# UAV_ARM.net
KiCad netlist of a schematic drawn in EAGLE
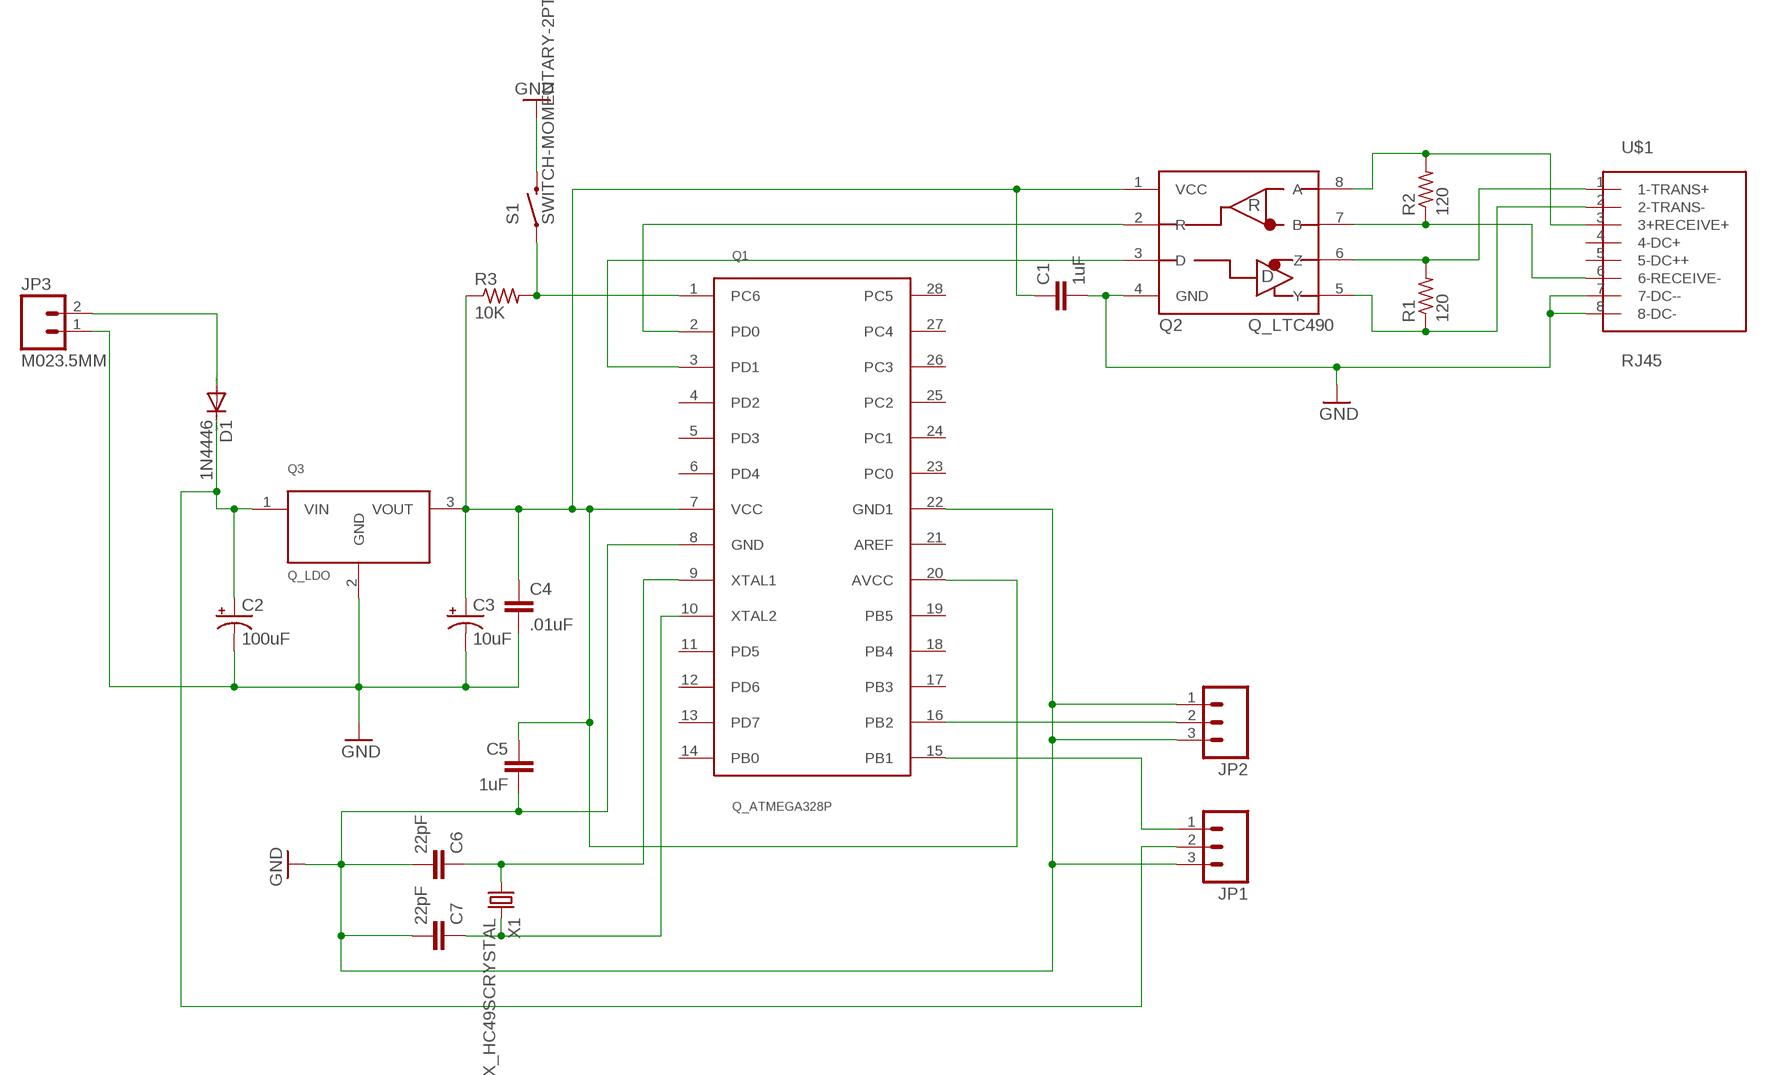
[diagram p0: schematic, sheet 1]

(export (version "E")
  (design (tool "Eeschema 10.0.6"))
  (components
    (comp (ref "C1")
      (value "1uF")
      (footprint "eagle-import:CAP-PTH-SMALL-KIT")
      (libsource (lib "eagle-import") (part "CAPKIT"))
    )
    (comp (ref "C2")
      (value "100uF")
      (footprint "eagle-import:CPOL-RADIAL-100UF-25V")
      (libsource (lib "eagle-import") (part "CAP_POLPTH1"))
    )
    (comp (ref "C3")
      (value "10uF")
      (footprint "eagle-import:CPOL-RADIAL-10UF-25V")
      (libsource (lib "eagle-import") (part "CAP_POLPTH2"))
    )
    (comp (ref "C4")
      (value ".01uF")
      (footprint "eagle-import:CAP-PTH-SMALL-KIT")
      (libsource (lib "eagle-import") (part "CAPKIT"))
    )
    (comp (ref "C5")
      (value "1uF")
      (footprint "eagle-import:CAP-PTH-SMALL-KIT")
      (libsource (lib "eagle-import") (part "CAPKIT"))
    )
    (comp (ref "C6")
      (value "22pF")
      (footprint "eagle-import:CAP-PTH-SMALL-KIT")
      (libsource (lib "eagle-import") (part "CAPKIT"))
    )
    (comp (ref "C7")
      (value "22pF")
      (footprint "eagle-import:CAP-PTH-SMALL-KIT")
      (libsource (lib "eagle-import") (part "CAPKIT"))
    )
    (comp (ref "D1")
      (value "1N4446")
      (footprint "eagle-import:DO35-10")
      (libsource (lib "eagle-import") (part "1N4446"))
    )
    (comp (ref "JP1")
      (value "M03POLAR")
      (footprint "eagle-import:MOLEX-1X3")
      (libsource (lib "eagle-import") (part "M03POLAR"))
    )
    (comp (ref "JP2")
      (value "M03POLAR")
      (footprint "eagle-import:MOLEX-1X3")
      (libsource (lib "eagle-import") (part "M03POLAR"))
    )
    (comp (ref "JP3")
      (value "M023.5MM")
      (footprint "eagle-import:SCREWTERMINAL-3.5MM-2")
      (libsource (lib "eagle-import") (part "M023.5MM"))
    )
    (comp (ref "Q1")
      (value "Q_ATMEGA328P")
      (footprint "eagle-import:DIP28")
      (libsource (lib "eagle-import") (part "Q_ATMEGA328P"))
    )
    (comp (ref "Q2")
      (value "Q_LTC490")
      (footprint "eagle-import:DIP8")
      (libsource (lib "eagle-import") (part "Q_LTC490"))
    )
    (comp (ref "Q3")
      (value "Q_LDO")
      (footprint "eagle-import:TO-220")
      (libsource (lib "eagle-import") (part "Q_LDO"))
    )
    (comp (ref "R1")
      (value "120")
      (footprint "eagle-import:0204_7")
      (libsource (lib "eagle-import") (part "R-US_0204/7"))
    )
    (comp (ref "R2")
      (value "120")
      (footprint "eagle-import:0204_7")
      (libsource (lib "eagle-import") (part "R-US_0204/7"))
    )
    (comp (ref "R3")
      (value "10K")
      (footprint "eagle-import:0204_7")
      (libsource (lib "eagle-import") (part "R-US_0204/7"))
    )
    (comp (ref "S1")
      (value "SWITCH-MOMENTARY-2PTH")
      (footprint "eagle-import:TACTILE-PTH")
      (libsource (lib "eagle-import") (part "SWITCH-MOMENTARY-2PTH"))
    )
    (comp (ref "U$1")
      (value "RJ45")
      (footprint "eagle-import:RJ45-CAT5E")
      (libsource (lib "eagle-import") (part "RJ45"))
    )
    (comp (ref "X1")
      (value "X_HC49SCRYSTAL")
      (footprint "eagle-import:HC-49")
      (libsource (lib "eagle-import") (part "X_HC49SCRYSTAL"))
    )
  )
  (nets
    (net (code "1") (name "GND") (class "Default")
      (node (ref "C1") (pin "2") (pinfunction "2_2") (pintype "passive"))
      (node (ref "C2") (pin "2") (pinfunction "-_2") (pintype "passive"))
      (node (ref "C3") (pin "2") (pinfunction "-_2") (pintype "passive"))
      (node (ref "C4") (pin "2") (pinfunction "2_2") (pintype "passive"))
      (node (ref "C5") (pin "2") (pinfunction "2_2") (pintype "passive"))
      (node (ref "C6") (pin "2") (pinfunction "2_2") (pintype "passive"))
      (node (ref "C7") (pin "2") (pinfunction "2_2") (pintype "passive"))
      (node (ref "JP1") (pin "3") (pinfunction "3_3") (pintype "passive"))
      (node (ref "JP2") (pin "1") (pinfunction "1_1") (pintype "passive"))
      (node (ref "JP2") (pin "3") (pinfunction "3_3") (pintype "passive"))
      (node (ref "JP3") (pin "1") (pinfunction "1_1") (pintype "passive"))
      (node (ref "Q1") (pin "22") (pinfunction "GND1_22") (pintype "bidirectional"))
      (node (ref "Q1") (pin "8") (pinfunction "GND_8") (pintype "bidirectional"))
      (node (ref "Q2") (pin "4") (pinfunction "GND_4") (pintype "bidirectional"))
      (node (ref "Q3") (pin "2") (pinfunction "GND_2") (pintype "bidirectional"))
      (node (ref "S1") (pin "3") (pinfunction "2_3") (pintype "passive"))
      (node (ref "U$1") (pin "7") (pinfunction "7-DC--_7") (pintype "bidirectional"))
      (node (ref "U$1") (pin "8") (pinfunction "8-DC-_8") (pintype "bidirectional"))
    )
    (net (code "2") (name "Net-(C2-+)") (class "Default")
      (node (ref "C2") (pin "1") (pinfunction "+_1") (pintype "passive"))
      (node (ref "D1") (pin "C") (pinfunction "C_C") (pintype "passive"))
      (node (ref "JP1") (pin "2") (pinfunction "2_2") (pintype "passive"))
      (node (ref "Q3") (pin "1") (pinfunction "VIN_1") (pintype "bidirectional"))
    )
    (net (code "3") (name "Net-(C3-+)") (class "Default")
      (node (ref "C1") (pin "1") (pinfunction "1_1") (pintype "passive"))
      (node (ref "C3") (pin "1") (pinfunction "+_1") (pintype "passive"))
      (node (ref "C4") (pin "1") (pinfunction "1_1") (pintype "passive"))
      (node (ref "C5") (pin "1") (pinfunction "1_1") (pintype "passive"))
      (node (ref "Q1") (pin "20") (pinfunction "AVCC_20") (pintype "bidirectional"))
      (node (ref "Q1") (pin "7") (pinfunction "VCC_7") (pintype "bidirectional"))
      (node (ref "Q2") (pin "1") (pinfunction "VCC_1") (pintype "bidirectional"))
      (node (ref "Q3") (pin "3") (pinfunction "VOUT_3") (pintype "bidirectional"))
      (node (ref "R3") (pin "1") (pinfunction "1_1") (pintype "passive"))
    )
    (net (code "4") (name "Net-(D1-PadA)") (class "Default")
      (node (ref "D1") (pin "A") (pinfunction "A_A") (pintype "passive"))
      (node (ref "JP3") (pin "2") (pinfunction "2_2") (pintype "passive"))
    )
    (net (code "5") (name "Net-(Q1-PB1)") (class "Default")
      (node (ref "JP1") (pin "1") (pinfunction "1_1") (pintype "passive"))
      (node (ref "Q1") (pin "15") (pinfunction "PB1_15") (pintype "bidirectional"))
    )
    (net (code "6") (name "Net-(Q1-PB2)") (class "Default")
      (node (ref "JP2") (pin "2") (pinfunction "2_2") (pintype "passive"))
      (node (ref "Q1") (pin "16") (pinfunction "PB2_16") (pintype "bidirectional"))
    )
    (net (code "7") (name "Net-(Q1-PC6)") (class "Default")
      (node (ref "Q1") (pin "1") (pinfunction "PC6_1") (pintype "bidirectional"))
      (node (ref "R3") (pin "2") (pinfunction "2_2") (pintype "passive"))
      (node (ref "S1") (pin "1") (pinfunction "1_1") (pintype "passive"))
    )
    (net (code "8") (name "Net-(Q1-PD0)") (class "Default")
      (node (ref "Q1") (pin "2") (pinfunction "PD0_2") (pintype "bidirectional"))
      (node (ref "Q2") (pin "2") (pinfunction "R_2") (pintype "bidirectional"))
    )
    (net (code "9") (name "Net-(Q1-PD1)") (class "Default")
      (node (ref "Q1") (pin "3") (pinfunction "PD1_3") (pintype "bidirectional"))
      (node (ref "Q2") (pin "3") (pinfunction "D_3") (pintype "bidirectional"))
    )
    (net (code "10") (name "Net-(Q1-XTAL1)") (class "Default")
      (node (ref "C6") (pin "1") (pinfunction "1_1") (pintype "passive"))
      (node (ref "Q1") (pin "9") (pinfunction "XTAL1_9") (pintype "bidirectional"))
      (node (ref "X1") (pin "P$1") (pinfunction "1_P$1") (pintype "passive"))
    )
    (net (code "11") (name "Net-(Q1-XTAL2)") (class "Default")
      (node (ref "C7") (pin "1") (pinfunction "1_1") (pintype "passive"))
      (node (ref "Q1") (pin "10") (pinfunction "XTAL2_10") (pintype "bidirectional"))
      (node (ref "X1") (pin "P$2") (pinfunction "2_P$2") (pintype "passive"))
    )
    (net (code "12") (name "Net-(Q2-A)") (class "Default")
      (node (ref "Q2") (pin "8") (pinfunction "A_8") (pintype "bidirectional"))
      (node (ref "R2") (pin "2") (pinfunction "2_2") (pintype "passive"))
      (node (ref "U$1") (pin "3") (pinfunction "3+RECEIVE+_3") (pintype "bidirectional"))
    )
    (net (code "13") (name "Net-(Q2-B)") (class "Default")
      (node (ref "Q2") (pin "7") (pinfunction "B_7") (pintype "bidirectional"))
      (node (ref "R2") (pin "1") (pinfunction "1_1") (pintype "passive"))
      (node (ref "U$1") (pin "6") (pinfunction "6-RECEIVE-_6") (pintype "bidirectional"))
    )
    (net (code "14") (name "Net-(Q2-Y)") (class "Default")
      (node (ref "Q2") (pin "5") (pinfunction "Y_5") (pintype "bidirectional"))
      (node (ref "R1") (pin "1") (pinfunction "1_1") (pintype "passive"))
      (node (ref "U$1") (pin "2") (pinfunction "2-TRANS-_2") (pintype "bidirectional"))
    )
    (net (code "15") (name "Net-(Q2-Z)") (class "Default")
      (node (ref "Q2") (pin "6") (pinfunction "Z_6") (pintype "bidirectional"))
      (node (ref "R1") (pin "2") (pinfunction "2_2") (pintype "passive"))
      (node (ref "U$1") (pin "1") (pinfunction "1-TRANS+_1") (pintype "bidirectional"))
    )
    (net (code "16") (name "unconnected-(Q1-AREF-Pad21)") (class "Default")
      (node (ref "Q1") (pin "21") (pinfunction "AREF_21") (pintype "bidirectional"))
    )
    (net (code "17") (name "unconnected-(Q1-PB0-Pad14)") (class "Default")
      (node (ref "Q1") (pin "14") (pinfunction "PB0_14") (pintype "bidirectional"))
    )
    (net (code "18") (name "unconnected-(Q1-PB3-Pad17)") (class "Default")
      (node (ref "Q1") (pin "17") (pinfunction "PB3_17") (pintype "bidirectional"))
    )
    (net (code "19") (name "unconnected-(Q1-PB4-Pad18)") (class "Default")
      (node (ref "Q1") (pin "18") (pinfunction "PB4_18") (pintype "bidirectional"))
    )
    (net (code "20") (name "unconnected-(Q1-PB5-Pad19)") (class "Default")
      (node (ref "Q1") (pin "19") (pinfunction "PB5_19") (pintype "bidirectional"))
    )
    (net (code "21") (name "unconnected-(Q1-PC0-Pad23)") (class "Default")
      (node (ref "Q1") (pin "23") (pinfunction "PC0_23") (pintype "bidirectional"))
    )
    (net (code "22") (name "unconnected-(Q1-PC1-Pad24)") (class "Default")
      (node (ref "Q1") (pin "24") (pinfunction "PC1_24") (pintype "bidirectional"))
    )
    (net (code "23") (name "unconnected-(Q1-PC2-Pad25)") (class "Default")
      (node (ref "Q1") (pin "25") (pinfunction "PC2_25") (pintype "bidirectional"))
    )
    (net (code "24") (name "unconnected-(Q1-PC3-Pad26)") (class "Default")
      (node (ref "Q1") (pin "26") (pinfunction "PC3_26") (pintype "bidirectional"))
    )
    (net (code "25") (name "unconnected-(Q1-PC4-Pad27)") (class "Default")
      (node (ref "Q1") (pin "27") (pinfunction "PC4_27") (pintype "bidirectional"))
    )
    (net (code "26") (name "unconnected-(Q1-PC5-Pad28)") (class "Default")
      (node (ref "Q1") (pin "28") (pinfunction "PC5_28") (pintype "bidirectional"))
    )
    (net (code "27") (name "unconnected-(Q1-PD2-Pad4)") (class "Default")
      (node (ref "Q1") (pin "4") (pinfunction "PD2_4") (pintype "bidirectional"))
    )
    (net (code "28") (name "unconnected-(Q1-PD3-Pad5)") (class "Default")
      (node (ref "Q1") (pin "5") (pinfunction "PD3_5") (pintype "bidirectional"))
    )
    (net (code "29") (name "unconnected-(Q1-PD4-Pad6)") (class "Default")
      (node (ref "Q1") (pin "6") (pinfunction "PD4_6") (pintype "bidirectional"))
    )
    (net (code "30") (name "unconnected-(Q1-PD5-Pad11)") (class "Default")
      (node (ref "Q1") (pin "11") (pinfunction "PD5_11") (pintype "bidirectional"))
    )
    (net (code "31") (name "unconnected-(Q1-PD6-Pad12)") (class "Default")
      (node (ref "Q1") (pin "12") (pinfunction "PD6_12") (pintype "bidirectional"))
    )
    (net (code "32") (name "unconnected-(Q1-PD7-Pad13)") (class "Default")
      (node (ref "Q1") (pin "13") (pinfunction "PD7_13") (pintype "bidirectional"))
    )
    (net (code "33") (name "unconnected-(U$1-4-DC+-Pad4)") (class "Default")
      (node (ref "U$1") (pin "4") (pinfunction "4-DC+_4") (pintype "bidirectional"))
    )
    (net (code "34") (name "unconnected-(U$1-5-DC++-Pad5)") (class "Default")
      (node (ref "U$1") (pin "5") (pinfunction "5-DC++_5") (pintype "bidirectional"))
    )
  )
)
